# TConnector.net
KiCad netlist of a schematic drawn in EAGLE
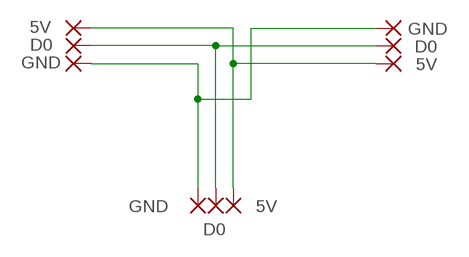
[diagram p0: schematic, sheet 1]

(export (version "E")
  (design (tool "Eeschema 10.0.6"))
  (components
    (comp (ref "5V@1")
      (value "5V")
      (footprint "eagle-import:SMD1,27-2,54")
      (libsource (lib "eagle-import") (part "SMD2"))
    )
    (comp (ref "5V@2")
      (value "5V")
      (footprint "eagle-import:SMD1,27-2,54")
      (libsource (lib "eagle-import") (part "SMD2"))
    )
    (comp (ref "5V@3")
      (value "5V")
      (footprint "eagle-import:SMD1,27-2,54")
      (libsource (lib "eagle-import") (part "SMD2"))
    )
    (comp (ref "D0")
      (value "D0")
      (footprint "eagle-import:SMD1,27-2,54")
      (libsource (lib "eagle-import") (part "SMD2"))
    )
    (comp (ref "GND@1")
      (value "GND")
      (footprint "eagle-import:SMD1,27-2,54")
      (libsource (lib "eagle-import") (part "SMD2"))
    )
    (comp (ref "GND@2")
      (value "GND")
      (footprint "eagle-import:SMD1,27-2,54")
      (libsource (lib "eagle-import") (part "SMD2"))
    )
    (comp (ref "GND@3")
      (value "GND")
      (footprint "eagle-import:SMD1,27-2,54")
      (libsource (lib "eagle-import") (part "SMD2"))
    )
    (comp (ref "PAD5")
      (value "D0")
      (footprint "eagle-import:SMD1,27-2,54")
      (libsource (lib "eagle-import") (part "SMD2"))
    )
    (comp (ref "PAD8")
      (value "D0")
      (footprint "eagle-import:SMD1,27-2,54")
      (libsource (lib "eagle-import") (part "SMD2"))
    )
  )
  (nets
    (net (code "1") (name "Net-(5V@1-P)") (class "Default")
      (node (ref "5V@1") (pin "1") (pinfunction "P_1") (pintype "passive"))
      (node (ref "5V@2") (pin "1") (pinfunction "P_1") (pintype "passive"))
      (node (ref "5V@3") (pin "1") (pinfunction "P_1") (pintype "passive"))
    )
    (net (code "2") (name "Net-(D0-P)") (class "Default")
      (node (ref "D0") (pin "1") (pinfunction "P_1") (pintype "passive"))
      (node (ref "PAD5") (pin "1") (pinfunction "P_1") (pintype "passive"))
      (node (ref "PAD8") (pin "1") (pinfunction "P_1") (pintype "passive"))
    )
    (net (code "3") (name "Net-(GND@1-P)") (class "Default")
      (node (ref "GND@1") (pin "1") (pinfunction "P_1") (pintype "passive"))
      (node (ref "GND@2") (pin "1") (pinfunction "P_1") (pintype "passive"))
      (node (ref "GND@3") (pin "1") (pinfunction "P_1") (pintype "passive"))
    )
  )
)
